# 07_RK3128_DDR.net
KiCad netlist of a schematic drawn in Altium Designer
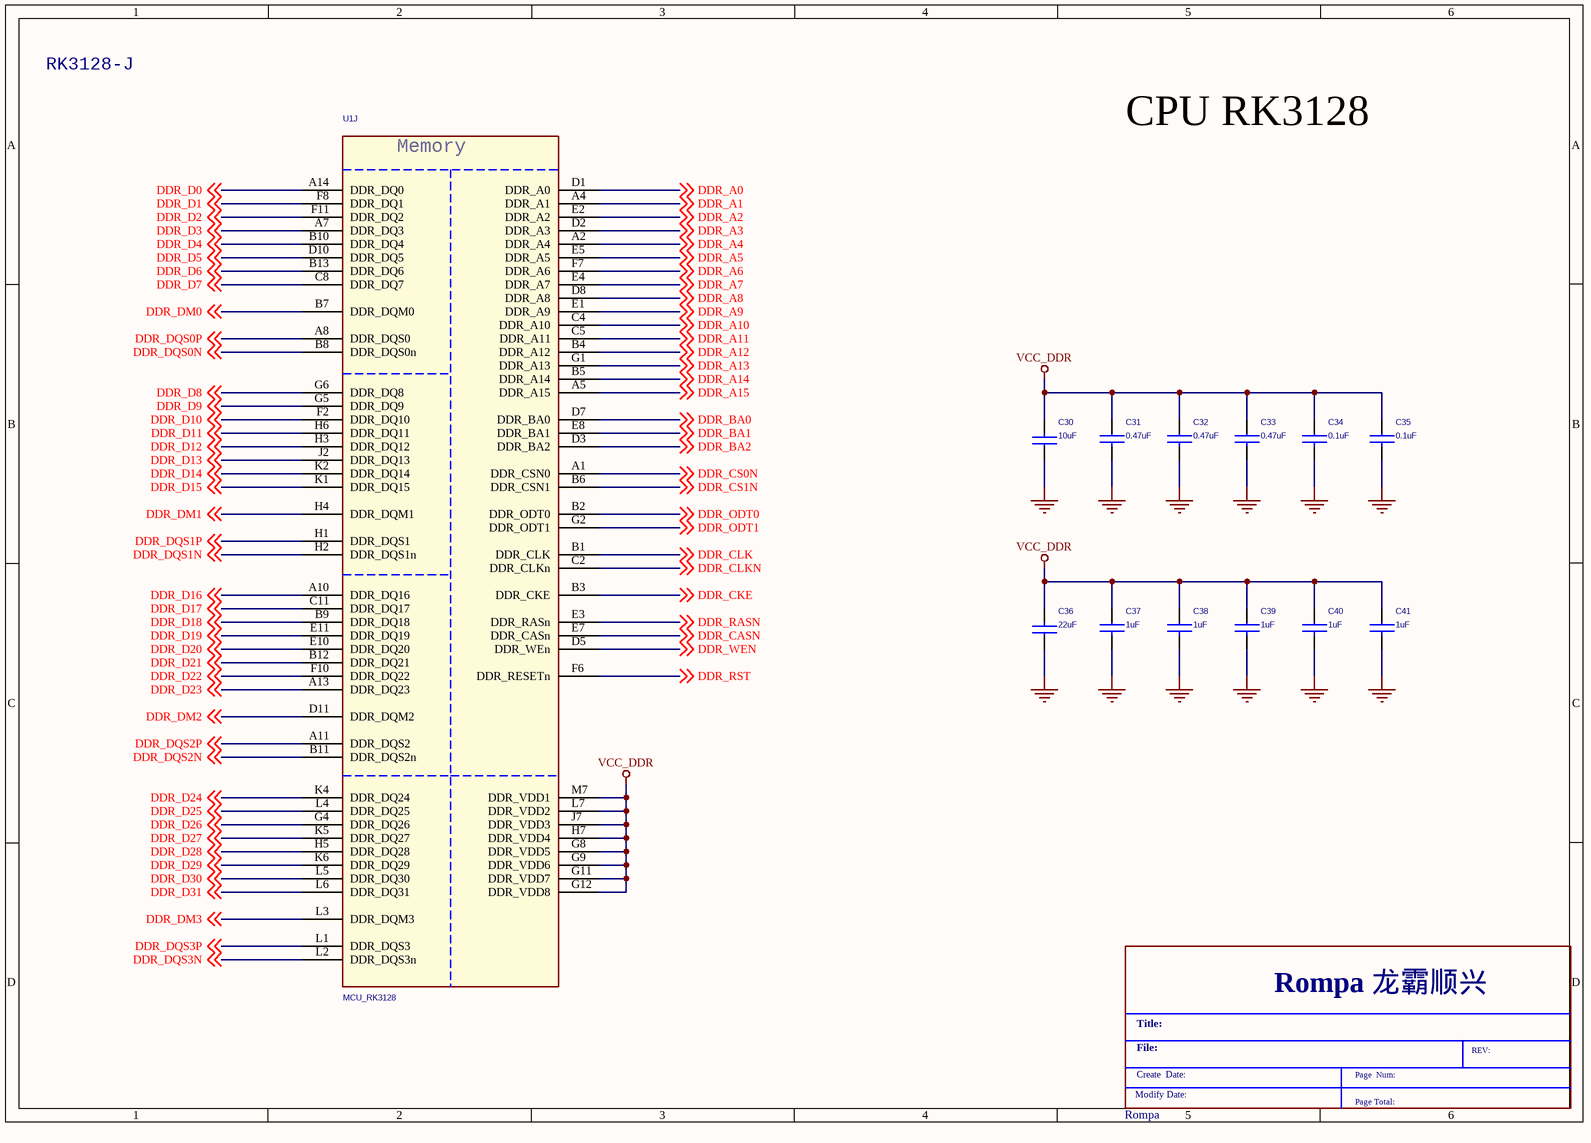
[diagram p0: 07_RK3128_DDR.SchDoc]

(export (version "E")
  (design (tool "Eeschema 10.0.6"))
  (components
    (comp (ref "C30")
      (value "10uF")
      (footprint "C0805")
      (description "RoHS CHIP CAP 10uF +10/-10% X5R")
      (libsource (lib "*") (part "CAP NP"))
    )
    (comp (ref "C31") (value "0.47uF") (footprint "C0402") (libsource (lib "*") (part "CAP NP_0")))
    (comp (ref "C32") (value "0.47uF") (footprint "C0402") (libsource (lib "*") (part "CAP NP_0")))
    (comp (ref "C33") (value "0.47uF") (footprint "C0402") (libsource (lib "*") (part "CAP NP_0")))
    (comp (ref "C34") (value "0.1uF") (footprint "C0402") (libsource (lib "*") (part "CAP NP_0")))
    (comp (ref "C35") (value "0.1uF") (footprint "C0402") (libsource (lib "*") (part "CAP NP_0")))
    (comp (ref "C36")
      (value "22uF")
      (footprint "C0805")
      (description "RoHS CHIP CAP 22uF +10/-10% X5R")
      (libsource (lib "*") (part "CAP NP"))
    )
    (comp (ref "C37") (value "1uF") (footprint "C0402") (libsource (lib "*") (part "CAP NP_0")))
    (comp (ref "C38") (value "1uF") (footprint "C0402") (libsource (lib "*") (part "CAP NP_0")))
    (comp (ref "C39") (value "1uF") (footprint "C0402") (libsource (lib "*") (part "CAP NP_0")))
    (comp (ref "C40") (value "1uF") (footprint "C0402") (libsource (lib "*") (part "CAP NP_0")))
    (comp (ref "C41") (value "1uF") (footprint "C0402") (libsource (lib "*") (part "CAP NP_0")))
    (comp (ref "U1")
      (value "MCU_RK3128")
      (footprint "BGA316-14X14-0.65")
      (libsource (lib "*") (part "MCU_RK3128"))
    )
  )
  (nets
    (net (code "1") (name "DDR_A0") (class "Default")
      (node (ref "U1") (pin "D1") (pinfunction "DDR_A0_D1") (pintype "passive"))
    )
    (net (code "2") (name "DDR_A1") (class "Default")
      (node (ref "U1") (pin "A4") (pinfunction "DDR_A1_A4") (pintype "passive"))
    )
    (net (code "3") (name "DDR_A2") (class "Default")
      (node (ref "U1") (pin "E2") (pinfunction "DDR_A2_E2") (pintype "passive"))
    )
    (net (code "4") (name "DDR_A3") (class "Default")
      (node (ref "U1") (pin "D2") (pinfunction "DDR_A3_D2") (pintype "passive"))
    )
    (net (code "5") (name "DDR_A4") (class "Default")
      (node (ref "U1") (pin "A2") (pinfunction "DDR_A4_A2") (pintype "passive"))
    )
    (net (code "6") (name "DDR_A5") (class "Default")
      (node (ref "U1") (pin "E5") (pinfunction "DDR_A5_E5") (pintype "passive"))
    )
    (net (code "7") (name "DDR_A6") (class "Default")
      (node (ref "U1") (pin "F7") (pinfunction "DDR_A6_F7") (pintype "passive"))
    )
    (net (code "8") (name "DDR_A7") (class "Default")
      (node (ref "U1") (pin "E4") (pinfunction "DDR_A7_E4") (pintype "passive"))
    )
    (net (code "9") (name "DDR_A8") (class "Default")
      (node (ref "U1") (pin "D8") (pinfunction "DDR_A8_D8") (pintype "passive"))
    )
    (net (code "10") (name "DDR_A9") (class "Default")
      (node (ref "U1") (pin "E1") (pinfunction "DDR_A9_E1") (pintype "passive"))
    )
    (net (code "11") (name "DDR_A10") (class "Default")
      (node (ref "U1") (pin "C4") (pinfunction "DDR_A10_C4") (pintype "passive"))
    )
    (net (code "12") (name "DDR_A11") (class "Default")
      (node (ref "U1") (pin "C5") (pinfunction "DDR_A11_C5") (pintype "passive"))
    )
    (net (code "13") (name "DDR_A12") (class "Default")
      (node (ref "U1") (pin "B4") (pinfunction "DDR_A12_B4") (pintype "passive"))
    )
    (net (code "14") (name "DDR_A13") (class "Default")
      (node (ref "U1") (pin "G1") (pinfunction "DDR_A13_G1") (pintype "passive"))
    )
    (net (code "15") (name "DDR_A14") (class "Default")
      (node (ref "U1") (pin "B5") (pinfunction "DDR_A14_B5") (pintype "passive"))
    )
    (net (code "16") (name "DDR_A15") (class "Default")
      (node (ref "U1") (pin "A5") (pinfunction "DDR_A15_A5") (pintype "passive"))
    )
    (net (code "17") (name "DDR_BA0") (class "Default")
      (node (ref "U1") (pin "D7") (pinfunction "DDR_BA0_D7") (pintype "passive"))
    )
    (net (code "18") (name "DDR_BA1") (class "Default")
      (node (ref "U1") (pin "E8") (pinfunction "DDR_BA1_E8") (pintype "passive"))
    )
    (net (code "19") (name "DDR_BA2") (class "Default")
      (node (ref "U1") (pin "D3") (pinfunction "DDR_BA2_D3") (pintype "passive"))
    )
    (net (code "20") (name "DDR_CASN") (class "Default")
      (node (ref "U1") (pin "E7") (pinfunction "DDR_CASn_E7") (pintype "passive"))
    )
    (net (code "21") (name "DDR_CKE") (class "Default")
      (node (ref "U1") (pin "B3") (pinfunction "DDR_CKE_B3") (pintype "passive"))
    )
    (net (code "22") (name "DDR_CLK") (class "Default")
      (node (ref "U1") (pin "B1") (pinfunction "DDR_CLK_B1") (pintype "passive"))
    )
    (net (code "23") (name "DDR_CLKN") (class "Default")
      (node (ref "U1") (pin "C2") (pinfunction "DDR_CLKn_C2") (pintype "passive"))
    )
    (net (code "24") (name "DDR_CS0N") (class "Default")
      (node (ref "U1") (pin "A1") (pinfunction "DDR_CSN0_A1") (pintype "passive"))
    )
    (net (code "25") (name "DDR_CS1N") (class "Default")
      (node (ref "U1") (pin "B6") (pinfunction "DDR_CSN1_B6") (pintype "passive"))
    )
    (net (code "26") (name "DDR_D0") (class "Default")
      (node (ref "U1") (pin "A14") (pinfunction "DDR_DQ0_A14") (pintype "passive"))
    )
    (net (code "27") (name "DDR_D1") (class "Default")
      (node (ref "U1") (pin "F8") (pinfunction "DDR_DQ1_F8") (pintype "passive"))
    )
    (net (code "28") (name "DDR_D2") (class "Default")
      (node (ref "U1") (pin "F11") (pinfunction "DDR_DQ2_F11") (pintype "passive"))
    )
    (net (code "29") (name "DDR_D3") (class "Default")
      (node (ref "U1") (pin "A7") (pinfunction "DDR_DQ3_A7") (pintype "passive"))
    )
    (net (code "30") (name "DDR_D4") (class "Default")
      (node (ref "U1") (pin "B10") (pinfunction "DDR_DQ4_B10") (pintype "passive"))
    )
    (net (code "31") (name "DDR_D5") (class "Default")
      (node (ref "U1") (pin "D10") (pinfunction "DDR_DQ5_D10") (pintype "passive"))
    )
    (net (code "32") (name "DDR_D6") (class "Default")
      (node (ref "U1") (pin "B13") (pinfunction "DDR_DQ6_B13") (pintype "passive"))
    )
    (net (code "33") (name "DDR_D7") (class "Default")
      (node (ref "U1") (pin "C8") (pinfunction "DDR_DQ7_C8") (pintype "passive"))
    )
    (net (code "34") (name "DDR_D8") (class "Default")
      (node (ref "U1") (pin "G6") (pinfunction "DDR_DQ8_G6") (pintype "passive"))
    )
    (net (code "35") (name "DDR_D9") (class "Default")
      (node (ref "U1") (pin "G5") (pinfunction "DDR_DQ9_G5") (pintype "passive"))
    )
    (net (code "36") (name "DDR_D10") (class "Default")
      (node (ref "U1") (pin "F2") (pinfunction "DDR_DQ10_F2") (pintype "passive"))
    )
    (net (code "37") (name "DDR_D11") (class "Default")
      (node (ref "U1") (pin "H6") (pinfunction "DDR_DQ11_H6") (pintype "passive"))
    )
    (net (code "38") (name "DDR_D12") (class "Default")
      (node (ref "U1") (pin "H3") (pinfunction "DDR_DQ12_H3") (pintype "passive"))
    )
    (net (code "39") (name "DDR_D13") (class "Default")
      (node (ref "U1") (pin "J2") (pinfunction "DDR_DQ13_J2") (pintype "passive"))
    )
    (net (code "40") (name "DDR_D14") (class "Default")
      (node (ref "U1") (pin "K2") (pinfunction "DDR_DQ14_K2") (pintype "passive"))
    )
    (net (code "41") (name "DDR_D15") (class "Default")
      (node (ref "U1") (pin "K1") (pinfunction "DDR_DQ15_K1") (pintype "passive"))
    )
    (net (code "42") (name "DDR_D16") (class "Default")
      (node (ref "U1") (pin "A10") (pinfunction "DDR_DQ16_A10") (pintype "passive"))
    )
    (net (code "43") (name "DDR_D17") (class "Default")
      (node (ref "U1") (pin "C11") (pinfunction "DDR_DQ17_C11") (pintype "passive"))
    )
    (net (code "44") (name "DDR_D18") (class "Default")
      (node (ref "U1") (pin "B9") (pinfunction "DDR_DQ18_B9") (pintype "passive"))
    )
    (net (code "45") (name "DDR_D19") (class "Default")
      (node (ref "U1") (pin "E11") (pinfunction "DDR_DQ19_E11") (pintype "passive"))
    )
    (net (code "46") (name "DDR_D20") (class "Default")
      (node (ref "U1") (pin "E10") (pinfunction "DDR_DQ20_E10") (pintype "passive"))
    )
    (net (code "47") (name "DDR_D21") (class "Default")
      (node (ref "U1") (pin "B12") (pinfunction "DDR_DQ21_B12") (pintype "passive"))
    )
    (net (code "48") (name "DDR_D22") (class "Default")
      (node (ref "U1") (pin "F10") (pinfunction "DDR_DQ22_F10") (pintype "passive"))
    )
    (net (code "49") (name "DDR_D23") (class "Default")
      (node (ref "U1") (pin "A13") (pinfunction "DDR_DQ23_A13") (pintype "passive"))
    )
    (net (code "50") (name "DDR_D24") (class "Default")
      (node (ref "U1") (pin "K4") (pinfunction "DDR_DQ24_K4") (pintype "passive"))
    )
    (net (code "51") (name "DDR_D25") (class "Default")
      (node (ref "U1") (pin "L4") (pinfunction "DDR_DQ25_L4") (pintype "passive"))
    )
    (net (code "52") (name "DDR_D26") (class "Default")
      (node (ref "U1") (pin "G4") (pinfunction "DDR_DQ26_G4") (pintype "passive"))
    )
    (net (code "53") (name "DDR_D27") (class "Default")
      (node (ref "U1") (pin "K5") (pinfunction "DDR_DQ27_K5") (pintype "passive"))
    )
    (net (code "54") (name "DDR_D28") (class "Default")
      (node (ref "U1") (pin "H5") (pinfunction "DDR_DQ28_H5") (pintype "passive"))
    )
    (net (code "55") (name "DDR_D29") (class "Default")
      (node (ref "U1") (pin "K6") (pinfunction "DDR_DQ29_K6") (pintype "passive"))
    )
    (net (code "56") (name "DDR_D30") (class "Default")
      (node (ref "U1") (pin "L5") (pinfunction "DDR_DQ30_L5") (pintype "passive"))
    )
    (net (code "57") (name "DDR_D31") (class "Default")
      (node (ref "U1") (pin "L6") (pinfunction "DDR_DQ31_L6") (pintype "passive"))
    )
    (net (code "58") (name "DDR_DM0") (class "Default")
      (node (ref "U1") (pin "B7") (pinfunction "DDR_DQM0_B7") (pintype "passive"))
    )
    (net (code "59") (name "DDR_DM1") (class "Default")
      (node (ref "U1") (pin "H4") (pinfunction "DDR_DQM1_H4") (pintype "passive"))
    )
    (net (code "60") (name "DDR_DM2") (class "Default")
      (node (ref "U1") (pin "D11") (pinfunction "DDR_DQM2_D11") (pintype "passive"))
    )
    (net (code "61") (name "DDR_DM3") (class "Default")
      (node (ref "U1") (pin "L3") (pinfunction "DDR_DQM3_L3") (pintype "passive"))
    )
    (net (code "62") (name "DDR_DQS0N") (class "Default")
      (node (ref "U1") (pin "B8") (pinfunction "DDR_DQS0n_B8") (pintype "passive"))
    )
    (net (code "63") (name "DDR_DQS0P") (class "Default")
      (node (ref "U1") (pin "A8") (pinfunction "DDR_DQS0_A8") (pintype "passive"))
    )
    (net (code "64") (name "DDR_DQS1N") (class "Default")
      (node (ref "U1") (pin "H2") (pinfunction "DDR_DQS1n_H2") (pintype "passive"))
    )
    (net (code "65") (name "DDR_DQS1P") (class "Default")
      (node (ref "U1") (pin "H1") (pinfunction "DDR_DQS1_H1") (pintype "passive"))
    )
    (net (code "66") (name "DDR_DQS2N") (class "Default")
      (node (ref "U1") (pin "B11") (pinfunction "DDR_DQS2n_B11") (pintype "passive"))
    )
    (net (code "67") (name "DDR_DQS2P") (class "Default")
      (node (ref "U1") (pin "A11") (pinfunction "DDR_DQS2_A11") (pintype "passive"))
    )
    (net (code "68") (name "DDR_DQS3N") (class "Default")
      (node (ref "U1") (pin "L2") (pinfunction "DDR_DQS3n_L2") (pintype "passive"))
    )
    (net (code "69") (name "DDR_DQS3P") (class "Default")
      (node (ref "U1") (pin "L1") (pinfunction "DDR_DQS3_L1") (pintype "passive"))
    )
    (net (code "70") (name "DDR_ODT0") (class "Default")
      (node (ref "U1") (pin "B2") (pinfunction "DDR_ODT0_B2") (pintype "passive"))
    )
    (net (code "71") (name "DDR_ODT1") (class "Default")
      (node (ref "U1") (pin "G2") (pinfunction "DDR_ODT1_G2") (pintype "passive"))
    )
    (net (code "72") (name "DDR_RASN") (class "Default")
      (node (ref "U1") (pin "E3") (pinfunction "DDR_RASn_E3") (pintype "passive"))
    )
    (net (code "73") (name "DDR_RST") (class "Default")
      (node (ref "U1") (pin "F6") (pinfunction "DDR_RESETn_F6") (pintype "passive"))
    )
    (net (code "74") (name "DDR_WEN") (class "Default")
      (node (ref "U1") (pin "D5") (pinfunction "DDR_WEn_D5") (pintype "passive"))
    )
    (net (code "75") (name "GND") (class "Default")
      (node (ref "C30") (pin "1") (pinfunction "1_1") (pintype "passive"))
      (node (ref "C31") (pin "2") (pinfunction "2_2") (pintype "passive"))
      (node (ref "C32") (pin "2") (pinfunction "2_2") (pintype "passive"))
      (node (ref "C33") (pin "2") (pinfunction "2_2") (pintype "passive"))
      (node (ref "C34") (pin "2") (pinfunction "2_2") (pintype "passive"))
      (node (ref "C35") (pin "2") (pinfunction "2_2") (pintype "passive"))
      (node (ref "C36") (pin "1") (pinfunction "1_1") (pintype "passive"))
      (node (ref "C37") (pin "2") (pinfunction "2_2") (pintype "passive"))
      (node (ref "C38") (pin "2") (pinfunction "2_2") (pintype "passive"))
      (node (ref "C39") (pin "2") (pinfunction "2_2") (pintype "passive"))
      (node (ref "C40") (pin "2") (pinfunction "2_2") (pintype "passive"))
      (node (ref "C41") (pin "2") (pinfunction "2_2") (pintype "passive"))
    )
    (net (code "76") (name "VCC_DDR") (class "Default")
      (node (ref "C30") (pin "2") (pinfunction "2_2") (pintype "passive"))
      (node (ref "C31") (pin "1") (pinfunction "1_1") (pintype "passive"))
      (node (ref "C32") (pin "1") (pinfunction "1_1") (pintype "passive"))
      (node (ref "C33") (pin "1") (pinfunction "1_1") (pintype "passive"))
      (node (ref "C34") (pin "1") (pinfunction "1_1") (pintype "passive"))
      (node (ref "C35") (pin "1") (pinfunction "1_1") (pintype "passive"))
      (node (ref "C36") (pin "2") (pinfunction "2_2") (pintype "passive"))
      (node (ref "C37") (pin "1") (pinfunction "1_1") (pintype "passive"))
      (node (ref "C38") (pin "1") (pinfunction "1_1") (pintype "passive"))
      (node (ref "C39") (pin "1") (pinfunction "1_1") (pintype "passive"))
      (node (ref "C40") (pin "1") (pinfunction "1_1") (pintype "passive"))
      (node (ref "C41") (pin "1") (pinfunction "1_1") (pintype "passive"))
      (node (ref "U1") (pin "G11") (pinfunction "DDR_VDD7_G11") (pintype "passive"))
      (node (ref "U1") (pin "G12") (pinfunction "DDR_VDD8_G12") (pintype "passive"))
      (node (ref "U1") (pin "G8") (pinfunction "DDR_VDD5_G8") (pintype "passive"))
      (node (ref "U1") (pin "G9") (pinfunction "DDR_VDD6_G9") (pintype "passive"))
      (node (ref "U1") (pin "H7") (pinfunction "DDR_VDD4_H7") (pintype "passive"))
      (node (ref "U1") (pin "J7") (pinfunction "DDR_VDD3_J7") (pintype "passive"))
      (node (ref "U1") (pin "L7") (pinfunction "DDR_VDD2_L7") (pintype "passive"))
      (node (ref "U1") (pin "M7") (pinfunction "DDR_VDD1_M7") (pintype "passive"))
    )
  )
)
